# ATmega16-TQFP44-breakout.net
KiCad netlist of a schematic drawn in EAGLE
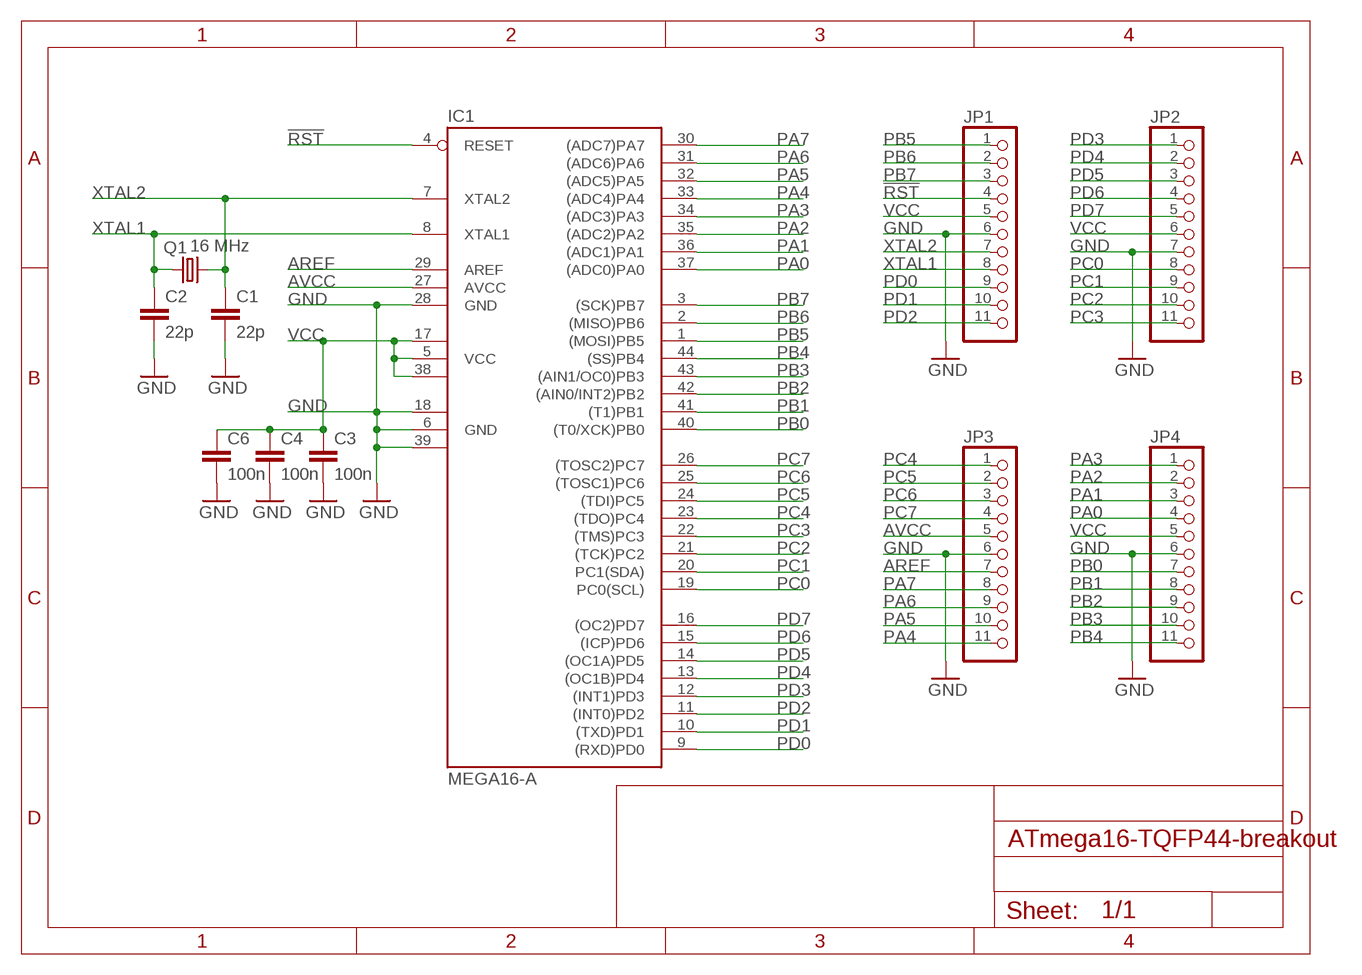
[diagram p0: schematic, sheet 1]

(export (version "E")
  (design (tool "Eeschema 10.0.6"))
  (components
    (comp (ref "C1")
      (value "22p")
      (footprint "eagle-import:C1206")
      (libsource (lib "eagle-import") (part "C-EUC1206"))
    )
    (comp (ref "C2")
      (value "22p")
      (footprint "eagle-import:C1206")
      (libsource (lib "eagle-import") (part "C-EUC1206"))
    )
    (comp (ref "C3")
      (value "100n")
      (footprint "eagle-import:C1206")
      (libsource (lib "eagle-import") (part "C-EUC1206"))
    )
    (comp (ref "C4")
      (value "100n")
      (footprint "eagle-import:C1206")
      (libsource (lib "eagle-import") (part "C-EUC1206"))
    )
    (comp (ref "C6")
      (value "100n")
      (footprint "eagle-import:C1206")
      (libsource (lib "eagle-import") (part "C-EUC1206"))
    )
    (comp (ref "IC1")
      (value "MEGA16-A")
      (footprint "eagle-import:TQFP44")
      (fields (field (name "MPN") "ATMEGA16-16AU"))
      (libsource (lib "eagle-import") (part "MEGA16-A"))
    )
    (comp (ref "JP1")
      (value "PINHD-1X11")
      (footprint "eagle-import:1X11")
      (libsource (lib "eagle-import") (part "PINHD-1X11"))
    )
    (comp (ref "JP2")
      (value "PINHD-1X11")
      (footprint "eagle-import:1X11")
      (libsource (lib "eagle-import") (part "PINHD-1X11"))
    )
    (comp (ref "JP3")
      (value "PINHD-1X11")
      (footprint "eagle-import:1X11")
      (libsource (lib "eagle-import") (part "PINHD-1X11"))
    )
    (comp (ref "JP4")
      (value "PINHD-1X11")
      (footprint "eagle-import:1X11")
      (libsource (lib "eagle-import") (part "PINHD-1X11"))
    )
    (comp (ref "Q1")
      (value "16 MHz")
      (footprint "eagle-import:HC49_S")
      (libsource (lib "eagle-import") (part "CRYSTALHC49S"))
    )
  )
  (nets
    (net (code "1") (name "/AREF") (class "Default")
      (node (ref "IC1") (pin "29") (pinfunction "AREF_29") (pintype "passive"))
      (node (ref "JP3") (pin "7") (pinfunction "7_7") (pintype "passive"))
    )
    (net (code "2") (name "/AVCC") (class "Default")
      (node (ref "IC1") (pin "27") (pinfunction "AVCC_27") (pintype "power_in"))
      (node (ref "JP3") (pin "5") (pinfunction "5_5") (pintype "passive"))
    )
    (net (code "3") (name "/PA0") (class "Default")
      (node (ref "IC1") (pin "37") (pinfunction "(ADC0)PA0_37") (pintype "bidirectional"))
      (node (ref "JP4") (pin "4") (pinfunction "4_4") (pintype "passive"))
    )
    (net (code "4") (name "/PA1") (class "Default")
      (node (ref "IC1") (pin "36") (pinfunction "(ADC1)PA1_36") (pintype "bidirectional"))
      (node (ref "JP4") (pin "3") (pinfunction "3_3") (pintype "passive"))
    )
    (net (code "5") (name "/PA2") (class "Default")
      (node (ref "IC1") (pin "35") (pinfunction "(ADC2)PA2_35") (pintype "bidirectional"))
      (node (ref "JP4") (pin "2") (pinfunction "2_2") (pintype "passive"))
    )
    (net (code "6") (name "/PA3") (class "Default")
      (node (ref "IC1") (pin "34") (pinfunction "(ADC3)PA3_34") (pintype "bidirectional"))
      (node (ref "JP4") (pin "1") (pinfunction "1_1") (pintype "passive"))
    )
    (net (code "7") (name "/PA4") (class "Default")
      (node (ref "IC1") (pin "33") (pinfunction "(ADC4)PA4_33") (pintype "bidirectional"))
      (node (ref "JP3") (pin "11") (pinfunction "11_11") (pintype "passive"))
    )
    (net (code "8") (name "/PA5") (class "Default")
      (node (ref "IC1") (pin "32") (pinfunction "(ADC5)PA5_32") (pintype "bidirectional"))
      (node (ref "JP3") (pin "10") (pinfunction "10_10") (pintype "passive"))
    )
    (net (code "9") (name "/PA6") (class "Default")
      (node (ref "IC1") (pin "31") (pinfunction "(ADC6)PA6_31") (pintype "bidirectional"))
      (node (ref "JP3") (pin "9") (pinfunction "9_9") (pintype "passive"))
    )
    (net (code "10") (name "/PA7") (class "Default")
      (node (ref "IC1") (pin "30") (pinfunction "(ADC7)PA7_30") (pintype "bidirectional"))
      (node (ref "JP3") (pin "8") (pinfunction "8_8") (pintype "passive"))
    )
    (net (code "11") (name "/PB0") (class "Default")
      (node (ref "IC1") (pin "40") (pinfunction "(T0/XCK)PB0_40") (pintype "bidirectional"))
      (node (ref "JP4") (pin "7") (pinfunction "7_7") (pintype "passive"))
    )
    (net (code "12") (name "/PB1") (class "Default")
      (node (ref "IC1") (pin "41") (pinfunction "(T1)PB1_41") (pintype "bidirectional"))
      (node (ref "JP4") (pin "8") (pinfunction "8_8") (pintype "passive"))
    )
    (net (code "13") (name "/PB2") (class "Default")
      (node (ref "IC1") (pin "42") (pinfunction "(AIN0/INT2)PB2_42") (pintype "bidirectional"))
      (node (ref "JP4") (pin "9") (pinfunction "9_9") (pintype "passive"))
    )
    (net (code "14") (name "/PB3") (class "Default")
      (node (ref "IC1") (pin "43") (pinfunction "(AIN1/OC0)PB3_43") (pintype "bidirectional"))
      (node (ref "JP4") (pin "10") (pinfunction "10_10") (pintype "passive"))
    )
    (net (code "15") (name "/PB4") (class "Default")
      (node (ref "IC1") (pin "44") (pinfunction "(SS)PB4_44") (pintype "bidirectional"))
      (node (ref "JP4") (pin "11") (pinfunction "11_11") (pintype "passive"))
    )
    (net (code "16") (name "/PB5") (class "Default")
      (node (ref "IC1") (pin "1") (pinfunction "(MOSI)PB5_1") (pintype "bidirectional"))
      (node (ref "JP1") (pin "1") (pinfunction "1_1") (pintype "passive"))
    )
    (net (code "17") (name "/PB6") (class "Default")
      (node (ref "IC1") (pin "2") (pinfunction "(MISO)PB6_2") (pintype "bidirectional"))
      (node (ref "JP1") (pin "2") (pinfunction "2_2") (pintype "passive"))
    )
    (net (code "18") (name "/PB7") (class "Default")
      (node (ref "IC1") (pin "3") (pinfunction "(SCK)PB7_3") (pintype "bidirectional"))
      (node (ref "JP1") (pin "3") (pinfunction "3_3") (pintype "passive"))
    )
    (net (code "19") (name "/PC0") (class "Default")
      (node (ref "IC1") (pin "19") (pinfunction "PC0(SCL)_19") (pintype "bidirectional"))
      (node (ref "JP2") (pin "8") (pinfunction "8_8") (pintype "passive"))
    )
    (net (code "20") (name "/PC1") (class "Default")
      (node (ref "IC1") (pin "20") (pinfunction "PC1(SDA)_20") (pintype "bidirectional"))
      (node (ref "JP2") (pin "9") (pinfunction "9_9") (pintype "passive"))
    )
    (net (code "21") (name "/PC2") (class "Default")
      (node (ref "IC1") (pin "21") (pinfunction "(TCK)PC2_21") (pintype "bidirectional"))
      (node (ref "JP2") (pin "10") (pinfunction "10_10") (pintype "passive"))
    )
    (net (code "22") (name "/PC3") (class "Default")
      (node (ref "IC1") (pin "22") (pinfunction "(TMS)PC3_22") (pintype "bidirectional"))
      (node (ref "JP2") (pin "11") (pinfunction "11_11") (pintype "passive"))
    )
    (net (code "23") (name "/PC4") (class "Default")
      (node (ref "IC1") (pin "23") (pinfunction "(TDO)PC4_23") (pintype "bidirectional"))
      (node (ref "JP3") (pin "1") (pinfunction "1_1") (pintype "passive"))
    )
    (net (code "24") (name "/PC5") (class "Default")
      (node (ref "IC1") (pin "24") (pinfunction "(TDI)PC5_24") (pintype "bidirectional"))
      (node (ref "JP3") (pin "2") (pinfunction "2_2") (pintype "passive"))
    )
    (net (code "25") (name "/PC6") (class "Default")
      (node (ref "IC1") (pin "25") (pinfunction "(TOSC1)PC6_25") (pintype "bidirectional"))
      (node (ref "JP3") (pin "3") (pinfunction "3_3") (pintype "passive"))
    )
    (net (code "26") (name "/PC7") (class "Default")
      (node (ref "IC1") (pin "26") (pinfunction "(TOSC2)PC7_26") (pintype "bidirectional"))
      (node (ref "JP3") (pin "4") (pinfunction "4_4") (pintype "passive"))
    )
    (net (code "27") (name "/PD0") (class "Default")
      (node (ref "IC1") (pin "9") (pinfunction "(RXD)PD0_9") (pintype "bidirectional"))
      (node (ref "JP1") (pin "9") (pinfunction "9_9") (pintype "passive"))
    )
    (net (code "28") (name "/PD1") (class "Default")
      (node (ref "IC1") (pin "10") (pinfunction "(TXD)PD1_10") (pintype "bidirectional"))
      (node (ref "JP1") (pin "10") (pinfunction "10_10") (pintype "passive"))
    )
    (net (code "29") (name "/PD2") (class "Default")
      (node (ref "IC1") (pin "11") (pinfunction "(INT0)PD2_11") (pintype "bidirectional"))
      (node (ref "JP1") (pin "11") (pinfunction "11_11") (pintype "passive"))
    )
    (net (code "30") (name "/PD3") (class "Default")
      (node (ref "IC1") (pin "12") (pinfunction "(INT1)PD3_12") (pintype "bidirectional"))
      (node (ref "JP2") (pin "1") (pinfunction "1_1") (pintype "passive"))
    )
    (net (code "31") (name "/PD4") (class "Default")
      (node (ref "IC1") (pin "13") (pinfunction "(OC1B)PD4_13") (pintype "bidirectional"))
      (node (ref "JP2") (pin "2") (pinfunction "2_2") (pintype "passive"))
    )
    (net (code "32") (name "/PD5") (class "Default")
      (node (ref "IC1") (pin "14") (pinfunction "(OC1A)PD5_14") (pintype "bidirectional"))
      (node (ref "JP2") (pin "3") (pinfunction "3_3") (pintype "passive"))
    )
    (net (code "33") (name "/PD6") (class "Default")
      (node (ref "IC1") (pin "15") (pinfunction "(ICP)PD6_15") (pintype "bidirectional"))
      (node (ref "JP2") (pin "4") (pinfunction "4_4") (pintype "passive"))
    )
    (net (code "34") (name "/PD7") (class "Default")
      (node (ref "IC1") (pin "16") (pinfunction "(OC2)PD7_16") (pintype "bidirectional"))
      (node (ref "JP2") (pin "5") (pinfunction "5_5") (pintype "passive"))
    )
    (net (code "35") (name "/VCC") (class "Default")
      (node (ref "C3") (pin "1") (pinfunction "1_1") (pintype "passive"))
      (node (ref "C4") (pin "1") (pinfunction "1_1") (pintype "passive"))
      (node (ref "C6") (pin "1") (pinfunction "1_1") (pintype "passive"))
      (node (ref "IC1") (pin "17") (pinfunction "VCC1_17") (pintype "power_in"))
      (node (ref "IC1") (pin "38") (pinfunction "VCC2_38") (pintype "power_in"))
      (node (ref "IC1") (pin "5") (pinfunction "VCC_5") (pintype "power_in"))
      (node (ref "JP1") (pin "5") (pinfunction "5_5") (pintype "passive"))
      (node (ref "JP2") (pin "6") (pinfunction "6_6") (pintype "passive"))
      (node (ref "JP4") (pin "5") (pinfunction "5_5") (pintype "passive"))
    )
    (net (code "36") (name "/XTAL1") (class "Default")
      (node (ref "C2") (pin "1") (pinfunction "1_1") (pintype "passive"))
      (node (ref "IC1") (pin "8") (pinfunction "XTAL1_8") (pintype "bidirectional"))
      (node (ref "JP1") (pin "8") (pinfunction "8_8") (pintype "passive"))
      (node (ref "Q1") (pin "1") (pinfunction "1_1") (pintype "passive"))
    )
    (net (code "37") (name "/XTAL2") (class "Default")
      (node (ref "C1") (pin "1") (pinfunction "1_1") (pintype "passive"))
      (node (ref "IC1") (pin "7") (pinfunction "XTAL2_7") (pintype "bidirectional"))
      (node (ref "JP1") (pin "7") (pinfunction "7_7") (pintype "passive"))
      (node (ref "Q1") (pin "2") (pinfunction "2_2") (pintype "passive"))
    )
    (net (code "38") (name "/~{RST}") (class "Default")
      (node (ref "IC1") (pin "4") (pinfunction "RESET_4") (pintype "input"))
      (node (ref "JP1") (pin "4") (pinfunction "4_4") (pintype "passive"))
    )
    (net (code "39") (name "GND") (class "Default")
      (node (ref "C1") (pin "2") (pinfunction "2_2") (pintype "passive"))
      (node (ref "C2") (pin "2") (pinfunction "2_2") (pintype "passive"))
      (node (ref "C3") (pin "2") (pinfunction "2_2") (pintype "passive"))
      (node (ref "C4") (pin "2") (pinfunction "2_2") (pintype "passive"))
      (node (ref "C6") (pin "2") (pinfunction "2_2") (pintype "passive"))
      (node (ref "IC1") (pin "18") (pinfunction "GND1_18") (pintype "power_in"))
      (node (ref "IC1") (pin "28") (pinfunction "GND_28") (pintype "power_in"))
      (node (ref "IC1") (pin "39") (pinfunction "GND2_39") (pintype "power_in"))
      (node (ref "IC1") (pin "6") (pinfunction "GND_6") (pintype "power_in"))
      (node (ref "JP1") (pin "6") (pinfunction "6_6") (pintype "passive"))
      (node (ref "JP2") (pin "7") (pinfunction "7_7") (pintype "passive"))
      (node (ref "JP3") (pin "6") (pinfunction "6_6") (pintype "passive"))
      (node (ref "JP4") (pin "6") (pinfunction "6_6") (pintype "passive"))
    )
  )
)
